# adapter_rfm95w_nrf242.net
KiCad netlist of a schematic drawn in EasyEDA Pro
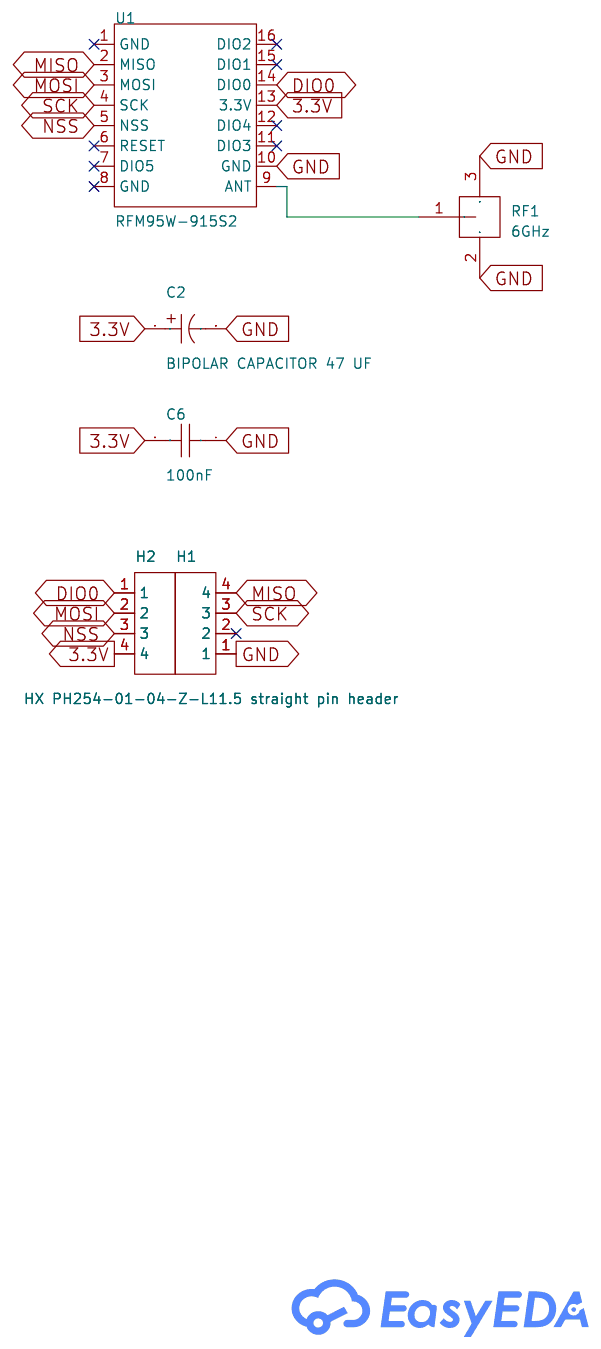
[diagram p0: schematic sheet]

(export (version "E")
  (design (tool "Eeschema 10.0.6"))
  (components
    (comp (ref "C2")
      (value "BIPOLAR CAPACITOR 47 UF")
      (footprint "easyedapro:CAP-TH_BD10.0-P5.00-D0.6-FD")
      (fields (field (name "Manufacturer") "Visaton"))
      (libsource (lib "easyedapro") (part "BIPOLAR CAPACITOR 22,0 UF"))
    )
    (comp (ref "C6")
      (value "100nF")
      (footprint "easyedapro:C0603")
      (libsource (lib "easyedapro") (part "CAP"))
    )
    (comp (ref "H1")
      (value "HX PH254-01-04-Z-L11.5 straight pin header")
      (footprint "easyedapro:HDR-TH_4P-HX-PH254-01-04-Z-L11.5")
      (fields (field (name "Manufacturer") "hanxia(韩下)"))
      (libsource (lib "easyedapro") (part "HX PH254-01-04-Z-L11.5 STRAIGHT PIN HEADER"))
    )
    (comp (ref "H2")
      (value "HX PH254-01-04-Z-L11.5 straight pin header")
      (footprint "easyedapro:HDR-TH_4P-HX-PH254-01-04-Z-L11.5")
      (fields (field (name "Manufacturer") "hanxia(韩下)"))
      (libsource (lib "easyedapro") (part "HX PH254-01-04-Z-L11.5 STRAIGHT PIN HEADER"))
    )
    (comp (ref "RF1")
      (value "6GHz")
      (footprint "easyedapro:IPEX-SMD_3P-L2.6-W2.6-LS3.0_MHFIANTENNACONNECTOR")
      (fields
        (field (name "Manufacturer Part") "HL2-IPEX1-SMT")
        (field (name "Manufacturer") "HenryTech(恒利泰)")
      )
      (libsource (lib "easyedapro") (part "HL2-IPEX1-SMT"))
    )
    (comp (ref "U1")
      (value "RFM95W-915S2")
      (footprint "easyedapro:WIRELM-SMD_16P-L16.0-W16.0-P2.00_LORA-CC68-915MHZ-TCXO")
      (fields (field (name "Manufacturer") "RF Solutions"))
      (libsource (lib "easyedapro") (part "RFM95W-915S2"))
    )
  )
  (nets
    (net (code "1") (name "3.3V") (class "Default")
      (node (ref "C2") (pin "1") (pinfunction "1_1") (pintype "input"))
      (node (ref "C6") (pin "2") (pinfunction "2_2") (pintype "input"))
      (node (ref "H2") (pin "4") (pinfunction "4_4") (pintype "unspecified"))
      (node (ref "U1") (pin "13") (pinfunction "3.3V_13") (pintype "unspecified"))
    )
    (net (code "2") (name "DIO0") (class "Default")
      (node (ref "H2") (pin "1") (pinfunction "1_1") (pintype "unspecified"))
      (node (ref "U1") (pin "14") (pinfunction "DIO0_14") (pintype "unspecified"))
    )
    (net (code "3") (name "GND") (class "Default")
      (node (ref "C2") (pin "2") (pinfunction "2_2") (pintype "input"))
      (node (ref "C6") (pin "1") (pinfunction "1_1") (pintype "input"))
      (node (ref "H1") (pin "1") (pinfunction "1_1") (pintype "unspecified"))
      (node (ref "RF1") (pin "2") (pinfunction "2_2") (pintype "unspecified"))
      (node (ref "RF1") (pin "3") (pinfunction "3_3") (pintype "unspecified"))
      (node (ref "U1") (pin "10") (pinfunction "GND_10") (pintype "unspecified"))
    )
    (net (code "4") (name "MISO") (class "Default")
      (node (ref "H1") (pin "4") (pinfunction "4_4") (pintype "unspecified"))
      (node (ref "U1") (pin "2") (pinfunction "MISO_2") (pintype "unspecified"))
    )
    (net (code "5") (name "MOSI") (class "Default")
      (node (ref "H2") (pin "2") (pinfunction "2_2") (pintype "unspecified"))
      (node (ref "U1") (pin "3") (pinfunction "MOSI_3") (pintype "unspecified"))
    )
    (net (code "6") (name "NSS") (class "Default")
      (node (ref "H2") (pin "3") (pinfunction "3_3") (pintype "unspecified"))
      (node (ref "U1") (pin "5") (pinfunction "NSS_5") (pintype "unspecified"))
    )
    (net (code "7") (name "Net-(U1-ANT)") (class "Default")
      (node (ref "RF1") (pin "1") (pinfunction "1_1") (pintype "unspecified"))
      (node (ref "U1") (pin "9") (pinfunction "ANT_9") (pintype "unspecified"))
    )
    (net (code "8") (name "SCK") (class "Default")
      (node (ref "H1") (pin "3") (pinfunction "3_3") (pintype "unspecified"))
      (node (ref "U1") (pin "4") (pinfunction "SCK_4") (pintype "unspecified"))
    )
    (net (code "9") (name "unconnected-(H1-Pad2)") (class "Default")
      (node (ref "H1") (pin "2") (pinfunction "2_2") (pintype "unspecified+no_connect"))
    )
    (net (code "10") (name "unconnected-(U1-DIO1-Pad15)") (class "Default")
      (node (ref "U1") (pin "15") (pinfunction "DIO1_15") (pintype "unspecified+no_connect"))
    )
    (net (code "11") (name "unconnected-(U1-DIO2-Pad16)") (class "Default")
      (node (ref "U1") (pin "16") (pinfunction "DIO2_16") (pintype "unspecified+no_connect"))
    )
    (net (code "12") (name "unconnected-(U1-DIO3-Pad11)") (class "Default")
      (node (ref "U1") (pin "11") (pinfunction "DIO3_11") (pintype "unspecified+no_connect"))
    )
    (net (code "13") (name "unconnected-(U1-DIO4-Pad12)") (class "Default")
      (node (ref "U1") (pin "12") (pinfunction "DIO4_12") (pintype "unspecified+no_connect"))
    )
    (net (code "14") (name "unconnected-(U1-DIO5-Pad7)") (class "Default")
      (node (ref "U1") (pin "7") (pinfunction "DIO5_7") (pintype "unspecified+no_connect"))
    )
    (net (code "15") (name "unconnected-(U1-GND-Pad1)") (class "Default")
      (node (ref "U1") (pin "1") (pinfunction "GND_1") (pintype "unspecified+no_connect"))
    )
    (net (code "16") (name "unconnected-(U1-GND-Pad8)") (class "Default")
      (node (ref "U1") (pin "8") (pinfunction "GND_8") (pintype "unspecified+no_connect"))
    )
    (net (code "17") (name "unconnected-(U1-RESET-Pad6)") (class "Default")
      (node (ref "U1") (pin "6") (pinfunction "RESET_6") (pintype "unspecified+no_connect"))
    )
  )
)
